# bGeigieNanoKit_V1_1r4c.net
KiCad netlist of a schematic drawn in EAGLE
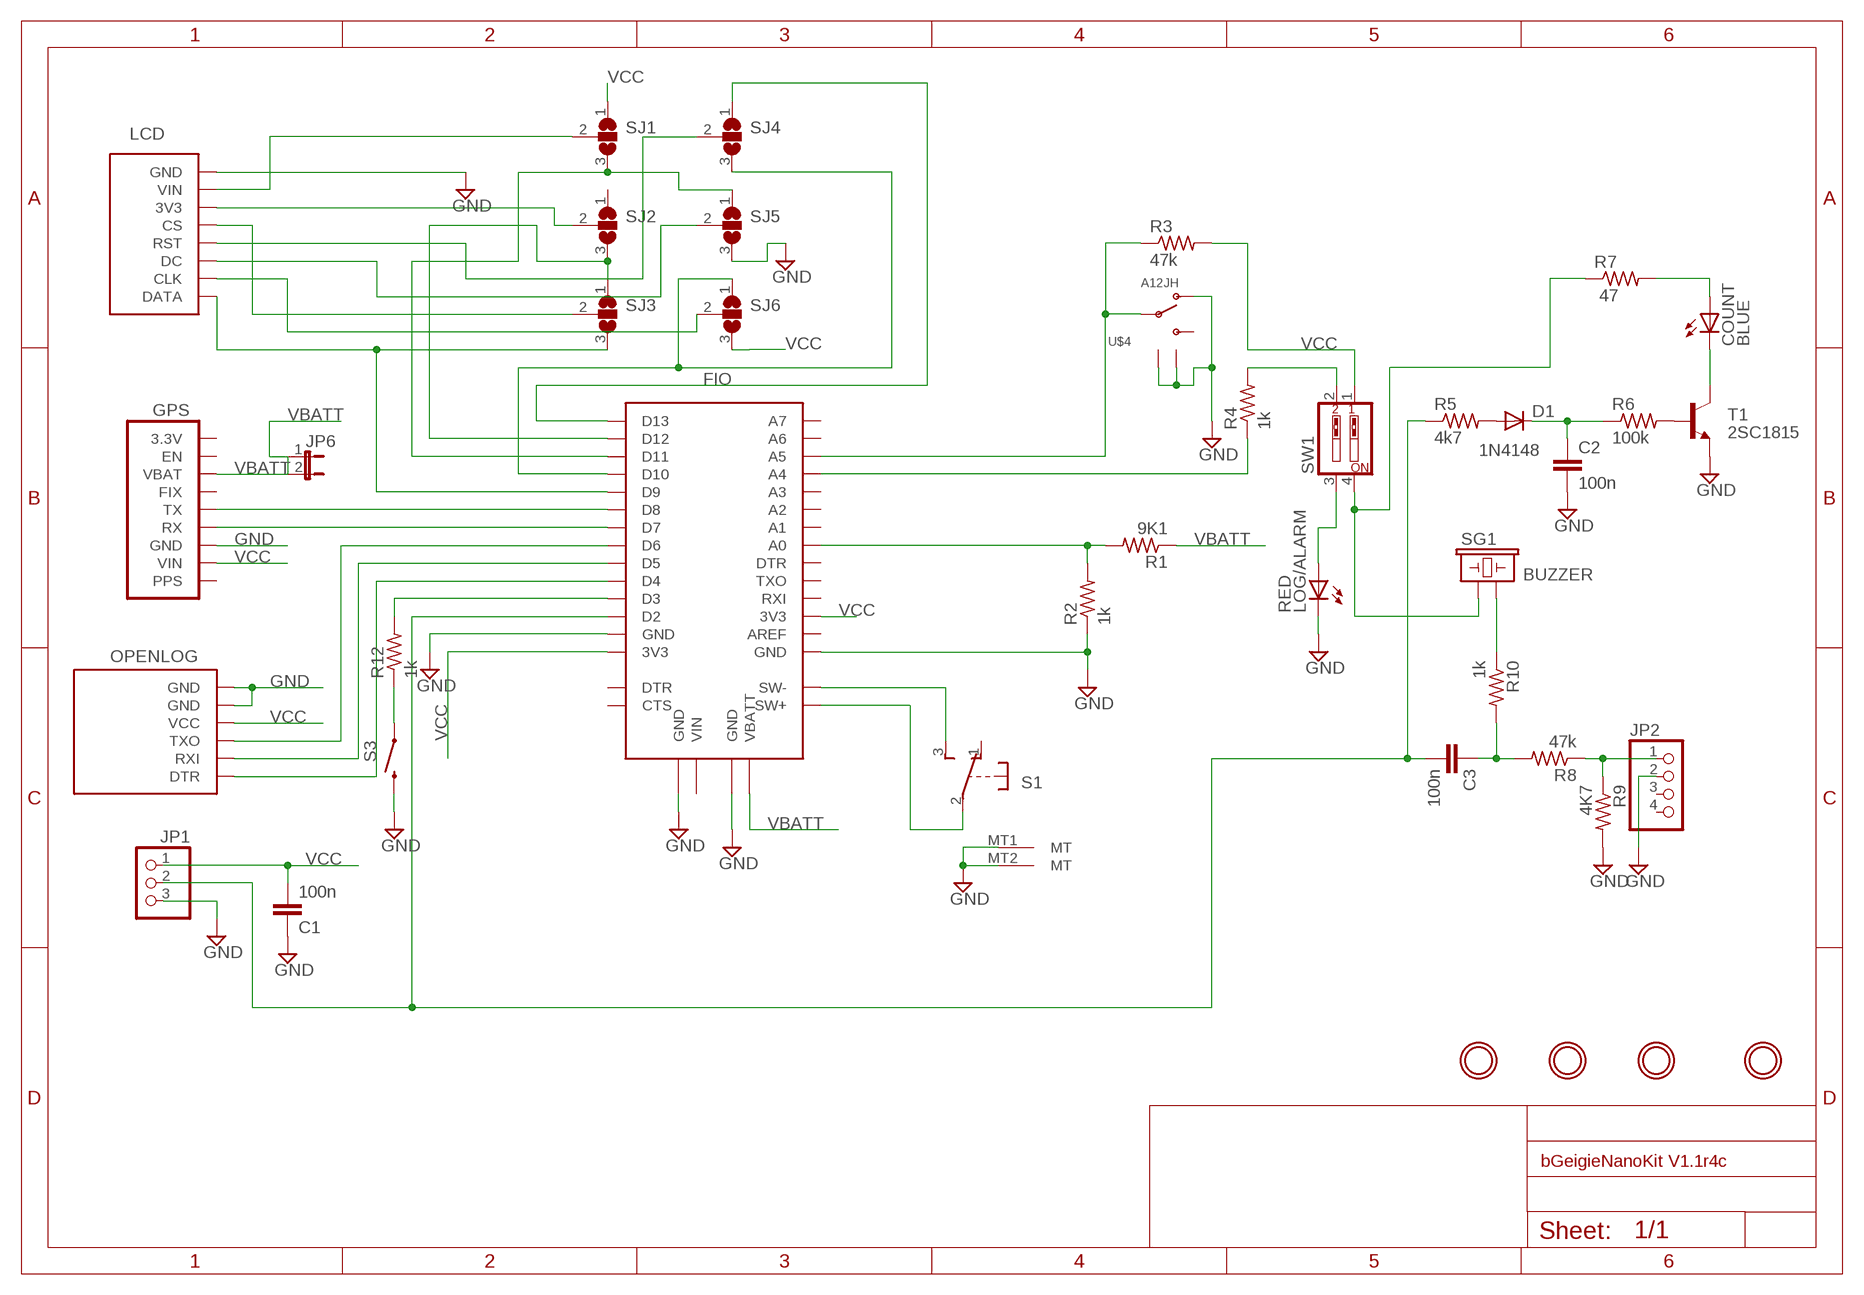
[diagram p0: schematic, sheet 1]

(export (version "E")
  (design (tool "Eeschema 10.0.6"))
  (components
    (comp (ref "C1")
      (value "100n")
      (footprint "eagle-import:C025-024X044")
      (libsource (lib "eagle-import") (part "C-EU025-024X044"))
    )
    (comp (ref "C2")
      (value "100n")
      (footprint "eagle-import:C025-024X044")
      (libsource (lib "eagle-import") (part "C-EU025-024X044"))
    )
    (comp (ref "C3")
      (value "100n")
      (footprint "eagle-import:C025-024X044")
      (libsource (lib "eagle-import") (part "C-EU025-024X044"))
    )
    (comp (ref "COUNT")
      (value "BLUE")
      (footprint "eagle-import:LED3MM")
      (libsource (lib "eagle-import") (part "LED3MM"))
    )
    (comp (ref "D1")
      (value "1N4148")
      (footprint "eagle-import:DO35-7")
      (fields (field (name "D1") "1N4148"))
      (libsource (lib "eagle-import") (part "1N4148DO35-7"))
    )
    (comp (ref "FIO")
      (value "FIO_SOCKETBOT")
      (footprint "eagle-import:FIO_V23_SOCKET_BOT")
      (libsource (lib "eagle-import") (part "FIO_SOCKETBOT"))
    )
    (comp (ref "GPS")
      (value "ULTIMATE_GPSTOP")
      (footprint "eagle-import:ULTIMATE_GPS_V3_TOP")
      (libsource (lib "eagle-import") (part "ULTIMATE_GPSTOP"))
    )
    (comp (ref "JP1")
      (value "PINHD-1X3/90")
      (footprint "eagle-import:1X03_90")
      (libsource (lib "eagle-import") (part "PINHD-1X3/90"))
    )
    (comp (ref "JP2")
      (value "HEADER-1X4ROUND")
      (footprint "eagle-import:1X04_ROUND")
      (libsource (lib "eagle-import") (part "HEADER-1X4ROUND"))
    )
    (comp (ref "JP6")
      (value "JUMPER-2SMD-NC")
      (footprint "eagle-import:SJ_2S")
      (libsource (lib "eagle-import") (part "JUMPER-2SMD-NC"))
    )
    (comp (ref "LCD")
      (value "SSD1306_128X64_V2_LCD1.3IN_LEVER")
      (footprint "eagle-import:SSD1306_128X64_1.3IN_LCD_LEVER")
      (libsource (lib "eagle-import") (part "SSD1306_128X64_V2_LCD1.3IN_LEVER"))
    )
    (comp (ref "LOG/ALARM")
      (value "RED")
      (footprint "eagle-import:LED3MM")
      (libsource (lib "eagle-import") (part "LED3MM"))
    )
    (comp (ref "OPENLOG")
      (value "OPENLOG")
      (footprint "eagle-import:OPENLOG")
      (libsource (lib "eagle-import") (part "OPENLOG"))
    )
    (comp (ref "R1")
      (value "9K1")
      (footprint "eagle-import:0207_10")
      (libsource (lib "eagle-import") (part "R-US_0207/10"))
    )
    (comp (ref "R2")
      (value "1k")
      (footprint "eagle-import:0207_10")
      (libsource (lib "eagle-import") (part "R-US_0207/10"))
    )
    (comp (ref "R3")
      (value "47k")
      (footprint "eagle-import:0207_10")
      (libsource (lib "eagle-import") (part "R-US_0207/10"))
    )
    (comp (ref "R4")
      (value "1k")
      (footprint "eagle-import:0207_10")
      (libsource (lib "eagle-import") (part "R-US_0207/10"))
    )
    (comp (ref "R5")
      (value "4k7")
      (footprint "eagle-import:0207_10")
      (libsource (lib "eagle-import") (part "R-US_0207/10"))
    )
    (comp (ref "R6")
      (value "100k")
      (footprint "eagle-import:0207_10")
      (libsource (lib "eagle-import") (part "R-US_0207/10"))
    )
    (comp (ref "R7")
      (value "47")
      (footprint "eagle-import:0207_10")
      (libsource (lib "eagle-import") (part "R-US_0207/10"))
    )
    (comp (ref "R8")
      (value "47k")
      (footprint "eagle-import:0207_10")
      (libsource (lib "eagle-import") (part "R-US_0207/10"))
    )
    (comp (ref "R9")
      (value "4K7")
      (footprint "eagle-import:0207_10")
      (libsource (lib "eagle-import") (part "R-US_0207/10"))
    )
    (comp (ref "R10")
      (value "1k")
      (footprint "eagle-import:0207_10")
      (libsource (lib "eagle-import") (part "R-US_0207/10"))
    )
    (comp (ref "R12")
      (value "1k")
      (footprint "eagle-import:0207_10")
      (libsource (lib "eagle-import") (part "R-US_0207/10"))
    )
    (comp (ref "S1")
      (value "S1")
      (footprint "eagle-import:EG1206")
      (libsource (lib "eagle-import") (part "EG1206"))
    )
    (comp (ref "S3")
      (value "SWITCH-MOMENTARY-2PTH")
      (footprint "eagle-import:TACTILE-PTH")
      (libsource (lib "eagle-import") (part "SWITCH-MOMENTARY-2PTH"))
    )
    (comp (ref "SG1")
      (value "BUZZER")
      (footprint "eagle-import:BUZZER-12MM")
      (libsource (lib "eagle-import") (part "BUZZERPTH"))
    )
    (comp (ref "SJ1")
      (value "SJ2W")
      (footprint "eagle-import:SJ_2")
      (libsource (lib "eagle-import") (part "SJ2W"))
    )
    (comp (ref "SJ2")
      (value "SJ2W")
      (footprint "eagle-import:SJ_2")
      (libsource (lib "eagle-import") (part "SJ2W"))
    )
    (comp (ref "SJ3")
      (value "SJ2W")
      (footprint "eagle-import:SJ_2")
      (libsource (lib "eagle-import") (part "SJ2W"))
    )
    (comp (ref "SJ4")
      (value "SJ2W")
      (footprint "eagle-import:SJ_2")
      (libsource (lib "eagle-import") (part "SJ2W"))
    )
    (comp (ref "SJ5")
      (value "SJ2W")
      (footprint "eagle-import:SJ_2")
      (libsource (lib "eagle-import") (part "SJ2W"))
    )
    (comp (ref "SJ6")
      (value "SJ2W")
      (footprint "eagle-import:SJ_2")
      (libsource (lib "eagle-import") (part "SJ2W"))
    )
    (comp (ref "SW1")
      (value "SW_DIP-2")
      (footprint "eagle-import:EDG-02")
      (libsource (lib "eagle-import") (part "SW_DIP-2"))
    )
    (comp (ref "T1")
      (value "2SC1815")
      (footprint "eagle-import:TO92-ECB")
      (libsource (lib "eagle-import") (part "2SC1815"))
    )
    (comp (ref "U$4")
      (value "A12JH")
      (footprint "eagle-import:A12AH")
      (libsource (lib "eagle-import") (part "A12JH"))
    )
    (comp (ref "U$6")
      (value "MOUNTINGHOLE3.0THIN")
      (footprint "eagle-import:MOUNTINGHOLE_3.0_PLATEDTHIN")
      (libsource (lib "eagle-import") (part "MOUNTINGHOLE3.0THIN"))
    )
    (comp (ref "U$7")
      (value "MOUNTINGHOLE3.0THIN")
      (footprint "eagle-import:MOUNTINGHOLE_3.0_PLATEDTHIN")
      (libsource (lib "eagle-import") (part "MOUNTINGHOLE3.0THIN"))
    )
    (comp (ref "U$8")
      (value "MOUNTINGHOLE3.0THIN")
      (footprint "eagle-import:MOUNTINGHOLE_3.0_PLATEDTHIN")
      (libsource (lib "eagle-import") (part "MOUNTINGHOLE3.0THIN"))
    )
    (comp (ref "U$9")
      (value "MOUNTINGHOLE3.0THIN")
      (footprint "eagle-import:MOUNTINGHOLE_3.0_PLATEDTHIN")
      (libsource (lib "eagle-import") (part "MOUNTINGHOLE3.0THIN"))
    )
  )
  (nets
    (net (code "1") (name "/3.3V") (class "Default")
      (node (ref "GPS") (pin "JP1$9") (pinfunction "3.3V_JP1$9") (pintype "power_in"))
    )
    (net (code "2") (name "/VBATT") (class "Default")
      (node (ref "FIO") (pin "JP2$2") (pinfunction "VBATT_JP2$2") (pintype "bidirectional"))
      (node (ref "GPS") (pin "JP1$7") (pinfunction "VBAT_JP1$7") (pintype "power_in"))
      (node (ref "JP6") (pin "1") (pinfunction "1_1") (pintype "passive"))
      (node (ref "JP6") (pin "2") (pinfunction "2_2") (pintype "passive"))
      (node (ref "R1") (pin "1") (pinfunction "1_1") (pintype "passive"))
    )
    (net (code "3") (name "/VCC") (class "Default")
      (node (ref "C1") (pin "2") (pinfunction "2_2") (pintype "passive"))
      (node (ref "FIO") (pin "JP1$1") (pinfunction "3V3_JP1$1") (pintype "power_in"))
      (node (ref "FIO") (pin "JP5$3") (pinfunction "3V3_JP5$3") (pintype "power_in"))
      (node (ref "GPS") (pin "JP1$2") (pinfunction "VIN_JP1$2") (pintype "power_in"))
      (node (ref "JP1") (pin "1") (pinfunction "1_1") (pintype "passive"))
      (node (ref "OPENLOG") (pin "JP1$4") (pinfunction "VCC_JP1$4") (pintype "power_in"))
      (node (ref "R3") (pin "2") (pinfunction "2_2") (pintype "passive"))
      (node (ref "SJ1") (pin "1") (pinfunction "1_1") (pintype "passive"))
      (node (ref "SJ6") (pin "3") (pinfunction "3_3") (pintype "passive"))
      (node (ref "SW1") (pin "1") (pinfunction "1_1") (pintype "passive"))
    )
    (net (code "4") (name "GND") (class "Default")
      (node (ref "C1") (pin "1") (pinfunction "1_1") (pintype "passive"))
      (node (ref "C2") (pin "2") (pinfunction "2_2") (pintype "passive"))
      (node (ref "FIO") (pin "JP1$2") (pinfunction "GND_JP1$2") (pintype "power_in"))
      (node (ref "FIO") (pin "JP2$1") (pinfunction "GND_JP2$1") (pintype "bidirectional"))
      (node (ref "FIO") (pin "JP5$1") (pinfunction "GND_JP5$1") (pintype "power_in"))
      (node (ref "FIO") (pin "JP6$1") (pinfunction "GND_JP6$1") (pintype "bidirectional"))
      (node (ref "GPS") (pin "JP1$3") (pinfunction "GND_JP1$3") (pintype "power_in"))
      (node (ref "GPS") (pin "U$8$P$1") (pinfunction "GND_U$8$P$1") (pintype "power_in"))
      (node (ref "GPS") (pin "U$9$P$1") (pinfunction "GND_U$9$P$1") (pintype "power_in"))
      (node (ref "JP1") (pin "3") (pinfunction "3_3") (pintype "passive"))
      (node (ref "JP2") (pin "2") (pinfunction "2_2") (pintype "passive"))
      (node (ref "LCD") (pin "JP1$8") (pinfunction "GND_JP1$8") (pintype "power_in"))
      (node (ref "LCD") (pin "U$23$P$1") (pinfunction "GND_U$23$P$1") (pintype "power_in"))
      (node (ref "LCD") (pin "U$26$P$1") (pinfunction "GND_U$26$P$1") (pintype "power_in"))
      (node (ref "LOG/ALARM") (pin "K") (pinfunction "C_K") (pintype "passive"))
      (node (ref "OPENLOG") (pin "JP1$5") (pinfunction "GND_JP1$5") (pintype "power_in"))
      (node (ref "OPENLOG") (pin "JP1$6") (pinfunction "GND_JP1$6") (pintype "power_in"))
      (node (ref "R2") (pin "1") (pinfunction "1_1") (pintype "passive"))
      (node (ref "R9") (pin "2") (pinfunction "2_2") (pintype "passive"))
      (node (ref "S1") (pin "MT1") (pinfunction "MT_MT1") (pintype "passive"))
      (node (ref "S1") (pin "MT2") (pinfunction "MT_MT2") (pintype "passive"))
      (node (ref "S3") (pin "3") (pinfunction "2_3") (pintype "passive"))
      (node (ref "SJ5") (pin "3") (pinfunction "3_3") (pintype "passive"))
      (node (ref "T1") (pin "E") (pinfunction "E_E") (pintype "passive"))
      (node (ref "U$4") (pin "P$1") (pinfunction "P$1_P$1") (pintype "passive"))
      (node (ref "U$4") (pin "P$4") (pinfunction "GND_P$4") (pintype "power_in"))
      (node (ref "U$4") (pin "P$5") (pinfunction "GND_P$5") (pintype "power_in"))
    )
    (net (code "5") (name "Net-(C2-Pad1)") (class "Default")
      (node (ref "C2") (pin "1") (pinfunction "1_1") (pintype "passive"))
      (node (ref "D1") (pin "C") (pinfunction "C_C") (pintype "passive"))
      (node (ref "R6") (pin "1") (pinfunction "1_1") (pintype "passive"))
    )
    (net (code "6") (name "Net-(C3-Pad1)") (class "Default")
      (node (ref "C3") (pin "1") (pinfunction "1_1") (pintype "passive"))
      (node (ref "R10") (pin "2") (pinfunction "2_2") (pintype "passive"))
      (node (ref "R8") (pin "2") (pinfunction "2_2") (pintype "passive"))
    )
    (net (code "7") (name "Net-(COUNT-C)") (class "Default")
      (node (ref "COUNT") (pin "K") (pinfunction "C_K") (pintype "passive"))
      (node (ref "T1") (pin "C") (pinfunction "C_C") (pintype "passive"))
    )
    (net (code "8") (name "Net-(COUNT-PadA)") (class "Default")
      (node (ref "COUNT") (pin "A") (pinfunction "A_A") (pintype "passive"))
      (node (ref "R7") (pin "2") (pinfunction "2_2") (pintype "passive"))
    )
    (net (code "9") (name "Net-(D1-PadA)") (class "Default")
      (node (ref "D1") (pin "A") (pinfunction "A_A") (pintype "passive"))
      (node (ref "R5") (pin "2") (pinfunction "2_2") (pintype "passive"))
    )
    (net (code "10") (name "Net-(FIO-A0)") (class "Default")
      (node (ref "FIO") (pin "JP5$7") (pinfunction "A0_JP5$7") (pintype "bidirectional"))
      (node (ref "R1") (pin "2") (pinfunction "2_2") (pintype "passive"))
      (node (ref "R2") (pin "2") (pinfunction "2_2") (pintype "passive"))
    )
    (net (code "11") (name "Net-(FIO-A4)") (class "Default")
      (node (ref "FIO") (pin "JP5$11") (pinfunction "A4_JP5$11") (pintype "bidirectional"))
      (node (ref "R4") (pin "1") (pinfunction "1_1") (pintype "passive"))
    )
    (net (code "12") (name "Net-(FIO-A5)") (class "Default")
      (node (ref "FIO") (pin "JP5$12") (pinfunction "A5_JP5$12") (pintype "bidirectional"))
      (node (ref "R3") (pin "1") (pinfunction "1_1") (pintype "passive"))
      (node (ref "U$4") (pin "P$2") (pinfunction "P$2_P$2") (pintype "passive"))
    )
    (net (code "13") (name "Net-(FIO-D2)") (class "Default")
      (node (ref "C3") (pin "2") (pinfunction "2_2") (pintype "passive"))
      (node (ref "FIO") (pin "JP1$3") (pinfunction "D2_JP1$3") (pintype "bidirectional"))
      (node (ref "JP1") (pin "2") (pinfunction "2_2") (pintype "passive"))
      (node (ref "R5") (pin "1") (pinfunction "1_1") (pintype "passive"))
    )
    (net (code "14") (name "Net-(FIO-D3)") (class "Default")
      (node (ref "FIO") (pin "JP1$4") (pinfunction "D3_JP1$4") (pintype "bidirectional"))
      (node (ref "R12") (pin "2") (pinfunction "2_2") (pintype "passive"))
    )
    (net (code "15") (name "Net-(FIO-D4)") (class "Default")
      (node (ref "FIO") (pin "JP1$5") (pinfunction "D4_JP1$5") (pintype "bidirectional"))
      (node (ref "OPENLOG") (pin "JP1$1") (pinfunction "DTR_JP1$1") (pintype "input"))
    )
    (net (code "16") (name "Net-(FIO-D5)") (class "Default")
      (node (ref "FIO") (pin "JP1$6") (pinfunction "D5_JP1$6") (pintype "bidirectional"))
      (node (ref "OPENLOG") (pin "JP1$2") (pinfunction "RXI_JP1$2") (pintype "input"))
    )
    (net (code "17") (name "Net-(FIO-D6)") (class "Default")
      (node (ref "FIO") (pin "JP1$7") (pinfunction "D6_JP1$7") (pintype "bidirectional"))
      (node (ref "OPENLOG") (pin "JP1$3") (pinfunction "TXO_JP1$3") (pintype "output"))
    )
    (net (code "18") (name "Net-(FIO-D7)") (class "Default")
      (node (ref "FIO") (pin "JP1$8") (pinfunction "D7_JP1$8") (pintype "bidirectional"))
      (node (ref "GPS") (pin "JP1$4") (pinfunction "RX_JP1$4") (pintype "input"))
    )
    (net (code "19") (name "Net-(FIO-D8)") (class "Default")
      (node (ref "FIO") (pin "JP1$9") (pinfunction "D8_JP1$9") (pintype "bidirectional"))
      (node (ref "GPS") (pin "JP1$5") (pinfunction "TX_JP1$5") (pintype "output"))
    )
    (net (code "20") (name "Net-(FIO-D9)") (class "Default")
      (node (ref "FIO") (pin "JP1$10") (pinfunction "D9_JP1$10") (pintype "bidirectional"))
      (node (ref "LCD") (pin "JP1$1") (pinfunction "DATA_JP1$1") (pintype "bidirectional"))
      (node (ref "SJ3") (pin "3") (pinfunction "3_3") (pintype "passive"))
    )
    (net (code "21") (name "Net-(FIO-D10)") (class "Default")
      (node (ref "FIO") (pin "JP1$11") (pinfunction "D10_JP1$11") (pintype "bidirectional"))
      (node (ref "SJ4") (pin "3") (pinfunction "3_3") (pintype "passive"))
      (node (ref "SJ6") (pin "1") (pinfunction "1_1") (pintype "passive"))
    )
    (net (code "22") (name "Net-(FIO-D11)") (class "Default")
      (node (ref "FIO") (pin "JP1$12") (pinfunction "D11_JP1$12") (pintype "bidirectional"))
      (node (ref "SJ1") (pin "3") (pinfunction "3_3") (pintype "passive"))
      (node (ref "SJ5") (pin "1") (pinfunction "1_1") (pintype "passive"))
    )
    (net (code "23") (name "Net-(FIO-D12)") (class "Default")
      (node (ref "FIO") (pin "JP1$13") (pinfunction "D12_JP1$13") (pintype "bidirectional"))
      (node (ref "SJ2") (pin "3") (pinfunction "3_3") (pintype "passive"))
      (node (ref "SJ3") (pin "1") (pinfunction "1_1") (pintype "passive"))
    )
    (net (code "24") (name "Net-(FIO-D13)") (class "Default")
      (node (ref "FIO") (pin "JP1$14") (pinfunction "D13_JP1$14") (pintype "bidirectional"))
      (node (ref "SJ4") (pin "1") (pinfunction "1_1") (pintype "passive"))
    )
    (net (code "25") (name "Net-(FIO-SW+)") (class "Default")
      (node (ref "FIO") (pin "JP7$2") (pinfunction "SW+_JP7$2") (pintype "bidirectional"))
      (node (ref "S1") (pin "2") (pinfunction "P_2") (pintype "passive"))
    )
    (net (code "26") (name "Net-(FIO-SW-)") (class "Default")
      (node (ref "FIO") (pin "JP7$1") (pinfunction "SW-_JP7$1") (pintype "bidirectional"))
      (node (ref "S1") (pin "3") (pinfunction "S_3") (pintype "passive"))
    )
    (net (code "27") (name "Net-(JP2-Pad1)") (class "Default")
      (node (ref "JP2") (pin "1") (pinfunction "1_1") (pintype "passive"))
      (node (ref "R8") (pin "1") (pinfunction "1_1") (pintype "passive"))
      (node (ref "R9") (pin "1") (pinfunction "1_1") (pintype "passive"))
    )
    (net (code "28") (name "Net-(LCD-3V3)") (class "Default")
      (node (ref "LCD") (pin "JP1$6") (pinfunction "3V3_JP1$6") (pintype "bidirectional"))
      (node (ref "SJ2") (pin "2") (pinfunction "2_2") (pintype "passive"))
    )
    (net (code "29") (name "Net-(LCD-CLK)") (class "Default")
      (node (ref "LCD") (pin "JP1$2") (pinfunction "CLK_JP1$2") (pintype "bidirectional"))
      (node (ref "SJ6") (pin "2") (pinfunction "2_2") (pintype "passive"))
    )
    (net (code "30") (name "Net-(LCD-CS)") (class "Default")
      (node (ref "LCD") (pin "JP1$5") (pinfunction "CS_JP1$5") (pintype "bidirectional"))
      (node (ref "SJ3") (pin "2") (pinfunction "2_2") (pintype "passive"))
    )
    (net (code "31") (name "Net-(LCD-DC)") (class "Default")
      (node (ref "LCD") (pin "JP1$3") (pinfunction "DC_JP1$3") (pintype "bidirectional"))
      (node (ref "SJ5") (pin "2") (pinfunction "2_2") (pintype "passive"))
    )
    (net (code "32") (name "Net-(LCD-RST)") (class "Default")
      (node (ref "LCD") (pin "JP1$4") (pinfunction "RST_JP1$4") (pintype "bidirectional"))
      (node (ref "SJ4") (pin "2") (pinfunction "2_2") (pintype "passive"))
    )
    (net (code "33") (name "Net-(LCD-VIN)") (class "Default")
      (node (ref "LCD") (pin "JP1$7") (pinfunction "VIN_JP1$7") (pintype "power_in"))
      (node (ref "SJ1") (pin "2") (pinfunction "2_2") (pintype "passive"))
    )
    (net (code "34") (name "Net-(LOG/ALARM-PadA)") (class "Default")
      (node (ref "LOG/ALARM") (pin "A") (pinfunction "A_A") (pintype "passive"))
      (node (ref "SW1") (pin "3") (pinfunction "3_3") (pintype "passive"))
    )
    (net (code "35") (name "Net-(R4-Pad2)") (class "Default")
      (node (ref "R4") (pin "2") (pinfunction "2_2") (pintype "passive"))
      (node (ref "SW1") (pin "2") (pinfunction "2_2") (pintype "passive"))
    )
    (net (code "36") (name "Net-(R6-Pad2)") (class "Default")
      (node (ref "R6") (pin "2") (pinfunction "2_2") (pintype "passive"))
      (node (ref "T1") (pin "B") (pinfunction "B_B") (pintype "passive"))
    )
    (net (code "37") (name "Net-(R12-Pad1)") (class "Default")
      (node (ref "R12") (pin "1") (pinfunction "1_1") (pintype "passive"))
      (node (ref "S3") (pin "1") (pinfunction "1_1") (pintype "passive"))
    )
    (net (code "38") (name "Net-(SG1-1)") (class "Default")
      (node (ref "R7") (pin "1") (pinfunction "1_1") (pintype "passive"))
      (node (ref "SG1") (pin "+") (pinfunction "1_+") (pintype "passive"))
      (node (ref "SW1") (pin "4") (pinfunction "4_4") (pintype "passive"))
    )
    (net (code "39") (name "Net-(SG1-2)") (class "Default")
      (node (ref "R10") (pin "1") (pinfunction "1_1") (pintype "passive"))
      (node (ref "SG1") (pin "-") (pinfunction "2_-") (pintype "passive"))
    )
    (net (code "40") (name "unconnected-(FIO-A1-PadJP5$8)") (class "Default")
      (node (ref "FIO") (pin "JP5$8") (pinfunction "A1_JP5$8") (pintype "bidirectional"))
    )
    (net (code "41") (name "unconnected-(FIO-A2-PadJP5$9)") (class "Default")
      (node (ref "FIO") (pin "JP5$9") (pinfunction "A2_JP5$9") (pintype "bidirectional"))
    )
    (net (code "42") (name "unconnected-(FIO-A3-PadJP5$10)") (class "Default")
      (node (ref "FIO") (pin "JP5$10") (pinfunction "A3_JP5$10") (pintype "bidirectional"))
    )
    (net (code "43") (name "unconnected-(FIO-A6-PadJP5$13)") (class "Default")
      (node (ref "FIO") (pin "JP5$13") (pinfunction "A6_JP5$13") (pintype "bidirectional"))
    )
    (net (code "44") (name "unconnected-(FIO-A7-PadJP5$14)") (class "Default")
      (node (ref "FIO") (pin "JP5$14") (pinfunction "A7_JP5$14") (pintype "bidirectional"))
    )
    (net (code "45") (name "unconnected-(FIO-AREF-PadJP5$2)") (class "Default")
      (node (ref "FIO") (pin "JP5$2") (pinfunction "AREF_JP5$2") (pintype "output"))
    )
    (net (code "46") (name "unconnected-(FIO-CTS-PadJP8$1)") (class "Default")
      (node (ref "FIO") (pin "JP8$1") (pinfunction "CTS_JP8$1") (pintype "bidirectional"))
    )
    (net (code "47") (name "unconnected-(FIO-DTR-PadJP5$6)") (class "Default")
      (node (ref "FIO") (pin "JP5$6") (pinfunction "DTR_JP5$6") (pintype "input"))
    )
    (net (code "48") (name "unconnected-(FIO-DTR-PadJP9$1)") (class "Default")
      (node (ref "FIO") (pin "JP9$1") (pinfunction "DTR_JP9$1") (pintype "bidirectional"))
    )
    (net (code "49") (name "unconnected-(FIO-RXI-PadJP5$4)") (class "Default")
      (node (ref "FIO") (pin "JP5$4") (pinfunction "RXI_JP5$4") (pintype "input"))
    )
    (net (code "50") (name "unconnected-(FIO-TXO-PadJP5$5)") (class "Default")
      (node (ref "FIO") (pin "JP5$5") (pinfunction "TXO_JP5$5") (pintype "output"))
    )
    (net (code "51") (name "unconnected-(FIO-VIN-PadJP6$2)") (class "Default")
      (node (ref "FIO") (pin "JP6$2") (pinfunction "VIN_JP6$2") (pintype "bidirectional"))
    )
    (net (code "52") (name "unconnected-(GPS-EN-PadJP1$8)") (class "Default")
      (node (ref "GPS") (pin "JP1$8") (pinfunction "EN_JP1$8") (pintype "input"))
    )
    (net (code "53") (name "unconnected-(GPS-FIX-PadJP1$6)") (class "Default")
      (node (ref "GPS") (pin "JP1$6") (pinfunction "FIX_JP1$6") (pintype "output"))
    )
    (net (code "54") (name "unconnected-(GPS-PPS-PadJP1$1)") (class "Default")
      (node (ref "GPS") (pin "JP1$1") (pinfunction "PPS_JP1$1") (pintype "output"))
    )
    (net (code "55") (name "unconnected-(JP2-Pad3)") (class "Default")
      (node (ref "JP2") (pin "3") (pinfunction "3_3") (pintype "passive"))
    )
    (net (code "56") (name "unconnected-(JP2-Pad4)") (class "Default")
      (node (ref "JP2") (pin "4") (pinfunction "4_4") (pintype "passive"))
    )
    (net (code "57") (name "unconnected-(S1A-O-Pad1)") (class "Default")
      (node (ref "S1") (pin "1") (pinfunction "O_1") (pintype "passive"))
    )
    (net (code "58") (name "unconnected-(SJ2-Pad1)") (class "Default")
      (node (ref "SJ2") (pin "1") (pinfunction "1_1") (pintype "passive"))
    )
    (net (code "59") (name "unconnected-(U$4-PadP$3)") (class "Default")
      (node (ref "U$4") (pin "P$3") (pinfunction "P$3_P$3") (pintype "passive"))
    )
  )
)
